# MCU_board_ATmega328p_v2_3.net
KiCad netlist of a schematic drawn in EAGLE
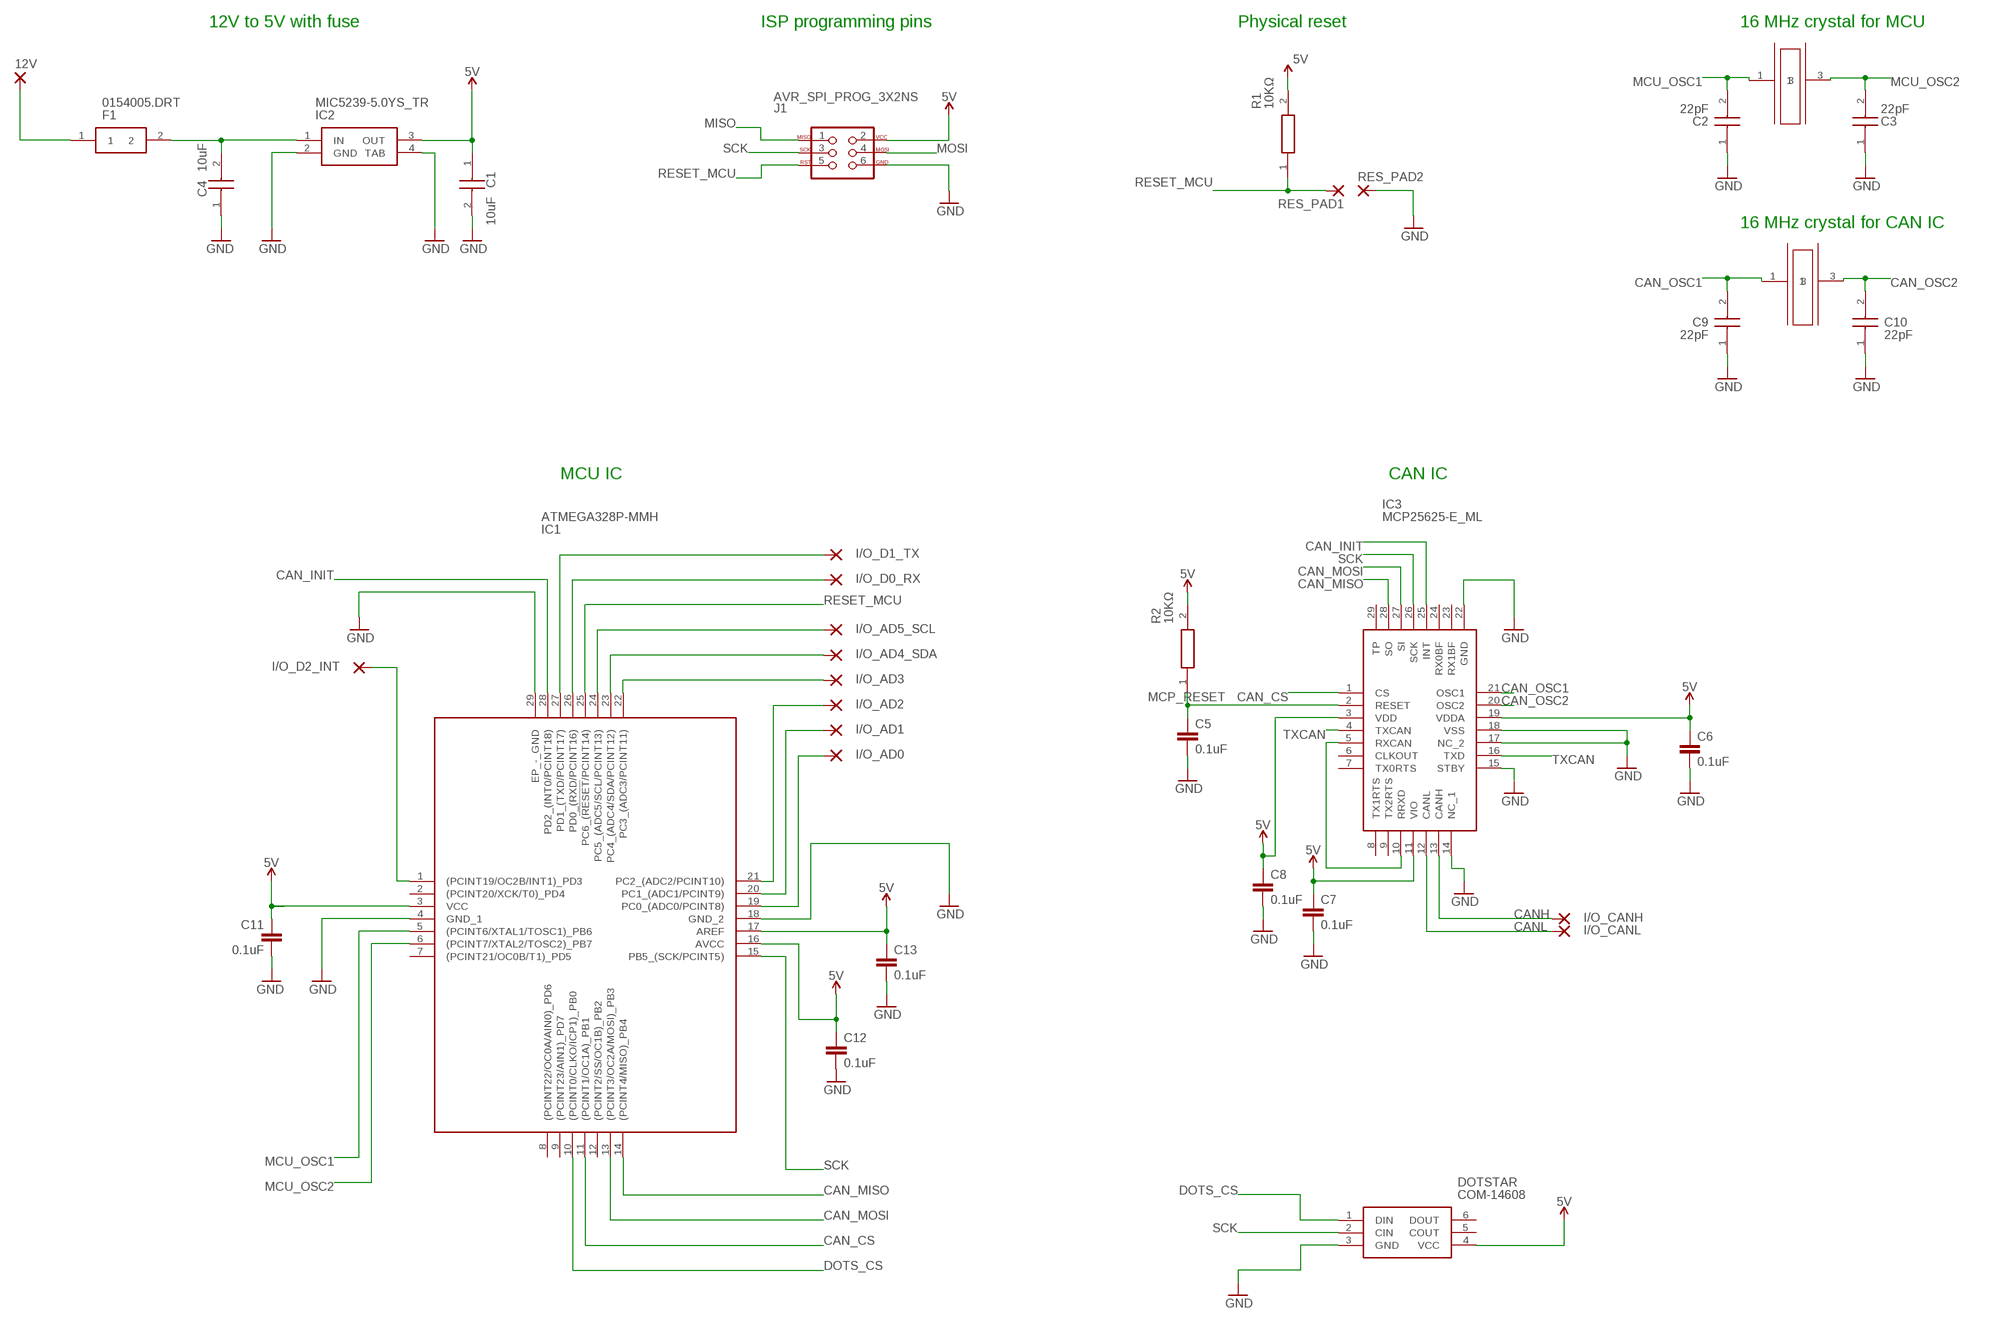
[diagram p0: schematic, sheet 1]

(export (version "E")
  (design (tool "Eeschema 10.0.6"))
  (components
    (comp (ref "12V")
      (value "2,15/1,0")
      (footprint "eagle-import:2,15_1,0")
      (libsource (lib "eagle-import") (part "2,15/1,0"))
    )
    (comp (ref "C1")
      (value "10uF")
      (footprint "eagle-import:CAPPM3216X180N")
      (fields (field (name "ARROW_PART_NUMBER") "T491A106K016AT") (field (name "RS_PART_NUMBER") "1696687"))
      (libsource (lib "eagle-import") (part "T491A106K016AT"))
    )
    (comp (ref "C2")
      (value "22pF")
      (footprint "eagle-import:CAPC3216X229N")
      (fields (field (name "ARROW_PART_NUMBER") "12066D106KAT2A") (field (name "RS_PART_NUMBER") "1356756"))
      (libsource (lib "eagle-import") (part "12066D106KAT2A"))
    )
    (comp (ref "C3")
      (value "22pF")
      (footprint "eagle-import:CAPC3216X229N")
      (fields (field (name "ARROW_PART_NUMBER") "12066D106KAT2A") (field (name "RS_PART_NUMBER") "1356756"))
      (libsource (lib "eagle-import") (part "12066D106KAT2A"))
    )
    (comp (ref "C4")
      (value "10uF")
      (footprint "eagle-import:CAPPM3216X180N")
      (fields (field (name "ARROW_PART_NUMBER") "T491A106K016AT") (field (name "RS_PART_NUMBER") "1696687"))
      (libsource (lib "eagle-import") (part "T491A106K016AT"))
    )
    (comp (ref "C5")
      (value "0.1uF")
      (footprint "eagle-import:C0603")
      (libsource (lib "eagle-import") (part "CC0603"))
    )
    (comp (ref "C6")
      (value "0.1uF")
      (footprint "eagle-import:C0603")
      (libsource (lib "eagle-import") (part "CC0603"))
    )
    (comp (ref "C7")
      (value "0.1uF")
      (footprint "eagle-import:C0603")
      (libsource (lib "eagle-import") (part "CC0603"))
    )
    (comp (ref "C8")
      (value "0.1uF")
      (footprint "eagle-import:C0603")
      (libsource (lib "eagle-import") (part "CC0603"))
    )
    (comp (ref "C9")
      (value "22pF")
      (footprint "eagle-import:CAPC3216X229N")
      (fields (field (name "ARROW_PART_NUMBER") "12066D106KAT2A") (field (name "RS_PART_NUMBER") "1356756"))
      (libsource (lib "eagle-import") (part "12066D106KAT2A"))
    )
    (comp (ref "C10")
      (value "22pF")
      (footprint "eagle-import:CAPC3216X229N")
      (fields (field (name "ARROW_PART_NUMBER") "12066D106KAT2A") (field (name "RS_PART_NUMBER") "1356756"))
      (libsource (lib "eagle-import") (part "12066D106KAT2A"))
    )
    (comp (ref "C11")
      (value "0.1uF")
      (footprint "eagle-import:C0603")
      (libsource (lib "eagle-import") (part "CC0603"))
    )
    (comp (ref "C12")
      (value "0.1uF")
      (footprint "eagle-import:C0603")
      (libsource (lib "eagle-import") (part "CC0603"))
    )
    (comp (ref "C13")
      (value "0.1uF")
      (footprint "eagle-import:C0603")
      (libsource (lib "eagle-import") (part "CC0603"))
    )
    (comp (ref "DOTSTAR")
      (value "COM-14608")
      (footprint "eagle-import:SON75P200X200X100-6N")
      (libsource (lib "eagle-import") (part "COM-14608"))
    )
    (comp (ref "F1")
      (value "0154005.DRT")
      (footprint "eagle-import:0154001.DRT")
      (fields (field (name "RS_PART_NUMBER") "2196260P"))
      (libsource (lib "eagle-import") (part "0154005.DRT"))
    )
    (comp (ref "I/O_AD0")
      (value "2,15/1,0")
      (footprint "eagle-import:2,15_1,0")
      (libsource (lib "eagle-import") (part "2,15/1,0"))
    )
    (comp (ref "I/O_AD1")
      (value "2,15/1,0")
      (footprint "eagle-import:2,15_1,0")
      (libsource (lib "eagle-import") (part "2,15/1,0"))
    )
    (comp (ref "I/O_AD2")
      (value "2,15/1,0")
      (footprint "eagle-import:2,15_1,0")
      (libsource (lib "eagle-import") (part "2,15/1,0"))
    )
    (comp (ref "I/O_AD3")
      (value "2,15/1,0")
      (footprint "eagle-import:2,15_1,0")
      (libsource (lib "eagle-import") (part "2,15/1,0"))
    )
    (comp (ref "I/O_AD4_SDA")
      (value "2,15/1,0")
      (footprint "eagle-import:2,15_1,0")
      (libsource (lib "eagle-import") (part "2,15/1,0"))
    )
    (comp (ref "I/O_AD5_SCL")
      (value "2,15/1,0")
      (footprint "eagle-import:2,15_1,0")
      (libsource (lib "eagle-import") (part "2,15/1,0"))
    )
    (comp (ref "I/O_CANH")
      (value "2,15/1,0")
      (footprint "eagle-import:2,15_1,0")
      (libsource (lib "eagle-import") (part "2,15/1,0"))
    )
    (comp (ref "I/O_CANL")
      (value "2,15/1,0")
      (footprint "eagle-import:2,15_1,0")
      (libsource (lib "eagle-import") (part "2,15/1,0"))
    )
    (comp (ref "I/O_D0_RX")
      (value "2,15/1,0")
      (footprint "eagle-import:2,15_1,0")
      (libsource (lib "eagle-import") (part "2,15/1,0"))
    )
    (comp (ref "I/O_D1_TX")
      (value "2,15/1,0")
      (footprint "eagle-import:2,15_1,0")
      (libsource (lib "eagle-import") (part "2,15/1,0"))
    )
    (comp (ref "I/O_D2_INT")
      (value "2,15/1,0")
      (footprint "eagle-import:2,15_1,0")
      (libsource (lib "eagle-import") (part "2,15/1,0"))
    )
    (comp (ref "IC1")
      (value "ATMEGA328P-MMH")
      (footprint "eagle-import:QFN45P400X400X100-29N")
      (fields (field (name "RS_PART_NUMBER") "1310272P"))
      (libsource (lib "eagle-import") (part "ATMEGA328P-MMH"))
    )
    (comp (ref "IC2")
      (value "MIC5239-5.0YS_TR")
      (footprint "eagle-import:SOT230P700X170-4N")
      (fields
        (field (name "ARROW_PART_NUMBER") "MIC5239-5.0YS TR")
        (field (name "RS_PART_NUMBER") "7275535P")
      )
      (libsource (lib "eagle-import") (part "MIC5239-5.0YS_TR"))
    )
    (comp (ref "IC3")
      (value "MCP25625-E_ML")
      (footprint "eagle-import:QFN65P600X600X100-29N")
      (fields (field (name "ARROW_PART_NUMBER") "MCP25625-E/ML") (field (name "RS_PART_NUMBER") "1654104"))
      (libsource (lib "eagle-import") (part "MCP25625-E_ML"))
    )
    (comp (ref "J1")
      (value "AVR_SPI_PROG_3X2NS")
      (footprint "eagle-import:2X3-NS")
      (libsource (lib "eagle-import") (part "AVR_SPI_PROG_3X2NS"))
    )
    (comp (ref "R1")
      (value "10KΩ")
      (footprint "eagle-import:RESC0603X28N")
      (fields (field (name "ARROW_PART_NUMBER") "CPF0201D10KC1") (field (name "RS_PART_NUMBER") "7549833"))
      (libsource (lib "eagle-import") (part "CPF0201D10KC1"))
    )
    (comp (ref "R2")
      (value "10KΩ")
      (footprint "eagle-import:RESC0603X28N")
      (fields (field (name "ARROW_PART_NUMBER") "CPF0201D10KC1") (field (name "RS_PART_NUMBER") "7549833"))
      (libsource (lib "eagle-import") (part "CPF0201D10KC1"))
    )
    (comp (ref "RES_PAD1")
      (value "SMD2")
      (footprint "eagle-import:SMD1,27-2,54")
      (libsource (lib "eagle-import") (part "SMD2"))
    )
    (comp (ref "RES_PAD2")
      (value "SMD2")
      (footprint "eagle-import:SMD1,27-2,54")
      (libsource (lib "eagle-import") (part "SMD2"))
    )
    (comp (ref "U$1")
      (value "FA-20H")
      (footprint "eagle-import:FA-20H")
      (libsource (lib "eagle-import") (part "FA-20H"))
    )
    (comp (ref "U$2")
      (value "FA-20H")
      (footprint "eagle-import:FA-20H")
      (libsource (lib "eagle-import") (part "FA-20H"))
    )
  )
  (nets
    (net (code "1") (name "/CANH") (class "Default")
      (node (ref "I/O_CANH") (pin "1") (pinfunction "P_1") (pintype "passive"))
      (node (ref "IC3") (pin "13") (pinfunction "CANH_13") (pintype "bidirectional"))
    )
    (net (code "2") (name "/CANL") (class "Default")
      (node (ref "I/O_CANL") (pin "1") (pinfunction "P_1") (pintype "passive"))
      (node (ref "IC3") (pin "12") (pinfunction "CANL_12") (pintype "bidirectional"))
    )
    (net (code "3") (name "/CAN_CS") (class "Default")
      (node (ref "IC1") (pin "11") (pinfunction "(PCINT1/OC1A)_PB1_11") (pintype "bidirectional"))
      (node (ref "IC3") (pin "1") (pinfunction "CS_1") (pintype "input"))
    )
    (net (code "4") (name "/CAN_INIT") (class "Default")
      (node (ref "IC1") (pin "28") (pinfunction "PD2_(INT0/PCINT18)_28") (pintype "bidirectional"))
      (node (ref "IC3") (pin "25") (pinfunction "INT_25") (pintype "input"))
    )
    (net (code "5") (name "/CAN_MISO") (class "Default")
      (node (ref "IC1") (pin "14") (pinfunction "(PCINT4/MISO)_PB4_14") (pintype "bidirectional"))
      (node (ref "IC3") (pin "28") (pinfunction "SO_28") (pintype "bidirectional"))
    )
    (net (code "6") (name "/CAN_MOSI") (class "Default")
      (node (ref "IC1") (pin "13") (pinfunction "(PCINT3/OC2A/MOSI)_PB3_13") (pintype "bidirectional"))
      (node (ref "IC3") (pin "27") (pinfunction "SI_27") (pintype "bidirectional"))
    )
    (net (code "7") (name "/CAN_OSC1") (class "Default")
      (node (ref "C9") (pin "2") (pinfunction "2_2") (pintype "bidirectional"))
      (node (ref "IC3") (pin "21") (pinfunction "OSC1_21") (pintype "bidirectional"))
      (node (ref "U$1") (pin "1") (pinfunction "1_1") (pintype "bidirectional"))
    )
    (net (code "8") (name "/CAN_OSC2") (class "Default")
      (node (ref "C10") (pin "2") (pinfunction "2_2") (pintype "bidirectional"))
      (node (ref "IC3") (pin "20") (pinfunction "OSC2_20") (pintype "bidirectional"))
      (node (ref "U$1") (pin "3") (pinfunction "3_3") (pintype "bidirectional"))
    )
    (net (code "9") (name "/DOTS_CS") (class "Default")
      (node (ref "DOTSTAR") (pin "1") (pinfunction "DIN_1") (pintype "bidirectional"))
      (node (ref "IC1") (pin "10") (pinfunction "(PCINT0/CLKO/ICP1)_PB0_10") (pintype "bidirectional"))
    )
    (net (code "10") (name "/MCP_RESET") (class "Default")
      (node (ref "C5") (pin "1") (pinfunction "1_1") (pintype "passive"))
      (node (ref "IC3") (pin "2") (pinfunction "RESET_2") (pintype "bidirectional"))
      (node (ref "R2") (pin "1") (pinfunction "1_1") (pintype "bidirectional"))
    )
    (net (code "11") (name "/MCU_OSC1") (class "Default")
      (node (ref "C2") (pin "2") (pinfunction "2_2") (pintype "bidirectional"))
      (node (ref "IC1") (pin "5") (pinfunction "(PCINT6/XTAL1/TOSC1)_PB6_5") (pintype "bidirectional"))
      (node (ref "U$2") (pin "1") (pinfunction "1_1") (pintype "bidirectional"))
    )
    (net (code "12") (name "/MCU_OSC2") (class "Default")
      (node (ref "C3") (pin "2") (pinfunction "2_2") (pintype "bidirectional"))
      (node (ref "IC1") (pin "6") (pinfunction "(PCINT7/XTAL2/TOSC2)_PB7_6") (pintype "bidirectional"))
      (node (ref "U$2") (pin "3") (pinfunction "3_3") (pintype "bidirectional"))
    )
    (net (code "13") (name "/MISO") (class "Default")
      (node (ref "J1") (pin "1") (pinfunction "1_1") (pintype "passive"))
    )
    (net (code "14") (name "/MOSI") (class "Default")
      (node (ref "J1") (pin "4") (pinfunction "4_4") (pintype "passive"))
    )
    (net (code "15") (name "/RESET_MCU") (class "Default")
      (node (ref "IC1") (pin "25") (pinfunction "PC6_(~{RESET}/PCINT14)_25") (pintype "bidirectional"))
      (node (ref "J1") (pin "5") (pinfunction "5_5") (pintype "passive"))
      (node (ref "R1") (pin "1") (pinfunction "1_1") (pintype "bidirectional"))
      (node (ref "RES_PAD1") (pin "1") (pinfunction "P_1") (pintype "passive"))
    )
    (net (code "16") (name "/SCK") (class "Default")
      (node (ref "DOTSTAR") (pin "2") (pinfunction "CIN_2") (pintype "bidirectional"))
      (node (ref "IC1") (pin "15") (pinfunction "PB5_(SCK/PCINT5)_15") (pintype "bidirectional"))
      (node (ref "IC3") (pin "26") (pinfunction "SCK_26") (pintype "bidirectional"))
      (node (ref "J1") (pin "3") (pinfunction "3_3") (pintype "passive"))
    )
    (net (code "17") (name "/TXCAN") (class "Default")
      (node (ref "IC3") (pin "16") (pinfunction "TXD_16") (pintype "bidirectional"))
      (node (ref "IC3") (pin "4") (pinfunction "TXCAN_4") (pintype "bidirectional"))
    )
    (net (code "18") (name "5V") (class "Default")
      (node (ref "C1") (pin "1") (pinfunction "K_1") (pintype "bidirectional"))
      (node (ref "C11") (pin "1") (pinfunction "1_1") (pintype "passive"))
      (node (ref "C12") (pin "1") (pinfunction "1_1") (pintype "passive"))
      (node (ref "C13") (pin "1") (pinfunction "1_1") (pintype "passive"))
      (node (ref "C6") (pin "1") (pinfunction "1_1") (pintype "passive"))
      (node (ref "C7") (pin "1") (pinfunction "1_1") (pintype "passive"))
      (node (ref "C8") (pin "1") (pinfunction "1_1") (pintype "passive"))
      (node (ref "DOTSTAR") (pin "4") (pinfunction "VCC_4") (pintype "bidirectional"))
      (node (ref "IC1") (pin "16") (pinfunction "AVCC_16") (pintype "bidirectional"))
      (node (ref "IC1") (pin "17") (pinfunction "AREF_17") (pintype "bidirectional"))
      (node (ref "IC1") (pin "3") (pinfunction "VCC_3") (pintype "bidirectional"))
      (node (ref "IC2") (pin "3") (pinfunction "OUT_3") (pintype "bidirectional"))
      (node (ref "IC3") (pin "11") (pinfunction "VIO_11") (pintype "bidirectional"))
      (node (ref "IC3") (pin "19") (pinfunction "VDDA_19") (pintype "power_in"))
      (node (ref "IC3") (pin "3") (pinfunction "VDD_3") (pintype "power_in"))
      (node (ref "J1") (pin "2") (pinfunction "2_2") (pintype "passive"))
      (node (ref "R1") (pin "2") (pinfunction "2_2") (pintype "bidirectional"))
      (node (ref "R2") (pin "2") (pinfunction "2_2") (pintype "bidirectional"))
    )
    (net (code "19") (name "GND") (class "Default")
      (node (ref "C1") (pin "2") (pinfunction "A_2") (pintype "bidirectional"))
      (node (ref "C10") (pin "1") (pinfunction "1_1") (pintype "bidirectional"))
      (node (ref "C11") (pin "2") (pinfunction "2_2") (pintype "passive"))
      (node (ref "C12") (pin "2") (pinfunction "2_2") (pintype "passive"))
      (node (ref "C13") (pin "2") (pinfunction "2_2") (pintype "passive"))
      (node (ref "C2") (pin "1") (pinfunction "1_1") (pintype "bidirectional"))
      (node (ref "C3") (pin "1") (pinfunction "1_1") (pintype "bidirectional"))
      (node (ref "C4") (pin "1") (pinfunction "K_1") (pintype "bidirectional"))
      (node (ref "C5") (pin "2") (pinfunction "2_2") (pintype "passive"))
      (node (ref "C6") (pin "2") (pinfunction "2_2") (pintype "passive"))
      (node (ref "C7") (pin "2") (pinfunction "2_2") (pintype "passive"))
      (node (ref "C8") (pin "2") (pinfunction "2_2") (pintype "passive"))
      (node (ref "C9") (pin "1") (pinfunction "1_1") (pintype "bidirectional"))
      (node (ref "DOTSTAR") (pin "3") (pinfunction "GND_3") (pintype "bidirectional"))
      (node (ref "IC1") (pin "18") (pinfunction "GND_2_18") (pintype "bidirectional"))
      (node (ref "IC1") (pin "29") (pinfunction "EP_-_GND_29") (pintype "bidirectional"))
      (node (ref "IC1") (pin "4") (pinfunction "GND_1_4") (pintype "bidirectional"))
      (node (ref "IC2") (pin "2") (pinfunction "GND_2") (pintype "bidirectional"))
      (node (ref "IC2") (pin "4") (pinfunction "TAB_4") (pintype "bidirectional"))
      (node (ref "IC3") (pin "14") (pinfunction "NC_1_14") (pintype "bidirectional"))
      (node (ref "IC3") (pin "15") (pinfunction "STBY_15") (pintype "bidirectional"))
      (node (ref "IC3") (pin "17") (pinfunction "NC_2_17") (pintype "bidirectional"))
      (node (ref "IC3") (pin "18") (pinfunction "VSS_18") (pintype "power_in"))
      (node (ref "IC3") (pin "22") (pinfunction "GND_22") (pintype "power_in"))
      (node (ref "J1") (pin "6") (pinfunction "6_6") (pintype "passive"))
      (node (ref "RES_PAD2") (pin "1") (pinfunction "P_1") (pintype "passive"))
    )
    (net (code "20") (name "Net-(12V-P)") (class "Default")
      (node (ref "12V") (pin "1") (pinfunction "P_1") (pintype "passive"))
      (node (ref "F1") (pin "1") (pinfunction "1_1") (pintype "bidirectional"))
    )
    (net (code "21") (name "Net-(C4-A)") (class "Default")
      (node (ref "C4") (pin "2") (pinfunction "A_2") (pintype "bidirectional"))
      (node (ref "F1") (pin "2") (pinfunction "2_2") (pintype "bidirectional"))
      (node (ref "IC2") (pin "1") (pinfunction "IN_1") (pintype "bidirectional"))
    )
    (net (code "22") (name "Net-(I/O_AD0-P)") (class "Default")
      (node (ref "I/O_AD0") (pin "1") (pinfunction "P_1") (pintype "passive"))
      (node (ref "IC1") (pin "19") (pinfunction "PC0_(ADC0/PCINT8)_19") (pintype "bidirectional"))
    )
    (net (code "23") (name "Net-(I/O_AD1-P)") (class "Default")
      (node (ref "I/O_AD1") (pin "1") (pinfunction "P_1") (pintype "passive"))
      (node (ref "IC1") (pin "20") (pinfunction "PC1_(ADC1/PCINT9)_20") (pintype "bidirectional"))
    )
    (net (code "24") (name "Net-(I/O_AD2-P)") (class "Default")
      (node (ref "I/O_AD2") (pin "1") (pinfunction "P_1") (pintype "passive"))
      (node (ref "IC1") (pin "21") (pinfunction "PC2_(ADC2/PCINT10)_21") (pintype "bidirectional"))
    )
    (net (code "25") (name "Net-(I/O_AD3-P)") (class "Default")
      (node (ref "I/O_AD3") (pin "1") (pinfunction "P_1") (pintype "passive"))
      (node (ref "IC1") (pin "22") (pinfunction "PC3_(ADC3/PCINT11)_22") (pintype "bidirectional"))
    )
    (net (code "26") (name "Net-(I/O_AD4_SDA-P)") (class "Default")
      (node (ref "I/O_AD4_SDA") (pin "1") (pinfunction "P_1") (pintype "passive"))
      (node (ref "IC1") (pin "23") (pinfunction "PC4_(ADC4/SDA/PCINT12)_23") (pintype "bidirectional"))
    )
    (net (code "27") (name "Net-(I/O_AD5_SCL-P)") (class "Default")
      (node (ref "I/O_AD5_SCL") (pin "1") (pinfunction "P_1") (pintype "passive"))
      (node (ref "IC1") (pin "24") (pinfunction "PC5_(ADC5/SCL/PCINT13)_24") (pintype "bidirectional"))
    )
    (net (code "28") (name "Net-(I/O_D0_RX-P)") (class "Default")
      (node (ref "I/O_D0_RX") (pin "1") (pinfunction "P_1") (pintype "passive"))
      (node (ref "IC1") (pin "26") (pinfunction "PD0_(RXD/PCINT16)_26") (pintype "bidirectional"))
    )
    (net (code "29") (name "Net-(I/O_D1_TX-P)") (class "Default")
      (node (ref "I/O_D1_TX") (pin "1") (pinfunction "P_1") (pintype "passive"))
      (node (ref "IC1") (pin "27") (pinfunction "PD1_(TXD/PCINT17)_27") (pintype "bidirectional"))
    )
    (net (code "30") (name "Net-(I/O_D2_INT-P)") (class "Default")
      (node (ref "I/O_D2_INT") (pin "1") (pinfunction "P_1") (pintype "passive"))
      (node (ref "IC1") (pin "1") (pinfunction "(PCINT19/OC2B/INT1)_PD3_1") (pintype "bidirectional"))
    )
    (net (code "31") (name "Net-(IC3-RRXD)") (class "Default")
      (node (ref "IC3") (pin "10") (pinfunction "RRXD_10") (pintype "bidirectional"))
      (node (ref "IC3") (pin "5") (pinfunction "RXCAN_5") (pintype "bidirectional"))
    )
    (net (code "32") (name "unconnected-(DOTSTAR-COUT-Pad5)") (class "Default")
      (node (ref "DOTSTAR") (pin "5") (pinfunction "COUT_5") (pintype "bidirectional"))
    )
    (net (code "33") (name "unconnected-(DOTSTAR-DOUT-Pad6)") (class "Default")
      (node (ref "DOTSTAR") (pin "6") (pinfunction "DOUT_6") (pintype "bidirectional"))
    )
    (net (code "34") (name "unconnected-(IC1-(PCINT2{slash}SS{slash}OC1B)_PB2-Pad12)") (class "Default")
      (node (ref "IC1") (pin "12") (pinfunction "(PCINT2/SS/OC1B)_PB2_12") (pintype "bidirectional"))
    )
    (net (code "35") (name "unconnected-(IC1-(PCINT20{slash}XCK{slash}T0)_PD4-Pad2)") (class "Default")
      (node (ref "IC1") (pin "2") (pinfunction "(PCINT20/XCK/T0)_PD4_2") (pintype "bidirectional"))
    )
    (net (code "36") (name "unconnected-(IC1-(PCINT21{slash}OC0B{slash}T1)_PD5-Pad7)") (class "Default")
      (node (ref "IC1") (pin "7") (pinfunction "(PCINT21/OC0B/T1)_PD5_7") (pintype "bidirectional"))
    )
    (net (code "37") (name "unconnected-(IC1-(PCINT22{slash}OC0A{slash}AIN0)_PD6-Pad8)") (class "Default")
      (node (ref "IC1") (pin "8") (pinfunction "(PCINT22/OC0A/AIN0)_PD6_8") (pintype "bidirectional"))
    )
    (net (code "38") (name "unconnected-(IC1-(PCINT23{slash}AIN1)_PD7-Pad9)") (class "Default")
      (node (ref "IC1") (pin "9") (pinfunction "(PCINT23/AIN1)_PD7_9") (pintype "bidirectional"))
    )
    (net (code "39") (name "unconnected-(IC3-CLKOUT-Pad6)") (class "Default")
      (node (ref "IC3") (pin "6") (pinfunction "CLKOUT_6") (pintype "output"))
    )
    (net (code "40") (name "unconnected-(IC3-RX0BF-Pad24)") (class "Default")
      (node (ref "IC3") (pin "24") (pinfunction "RX0BF_24") (pintype "bidirectional"))
    )
    (net (code "41") (name "unconnected-(IC3-RX1BF-Pad23)") (class "Default")
      (node (ref "IC3") (pin "23") (pinfunction "RX1BF_23") (pintype "bidirectional"))
    )
    (net (code "42") (name "unconnected-(IC3-TP-Pad29)") (class "Default")
      (node (ref "IC3") (pin "29") (pinfunction "TP_29") (pintype "bidirectional"))
    )
    (net (code "43") (name "unconnected-(IC3-TX0RTS-Pad7)") (class "Default")
      (node (ref "IC3") (pin "7") (pinfunction "TX0RTS_7") (pintype "bidirectional"))
    )
    (net (code "44") (name "unconnected-(IC3-TX1RTS-Pad8)") (class "Default")
      (node (ref "IC3") (pin "8") (pinfunction "TX1RTS_8") (pintype "bidirectional"))
    )
    (net (code "45") (name "unconnected-(IC3-TX2RTS-Pad9)") (class "Default")
      (node (ref "IC3") (pin "9") (pinfunction "TX2RTS_9") (pintype "bidirectional"))
    )
  )
)
